# OLED_Board.net
KiCad netlist of a schematic drawn in EAGLE
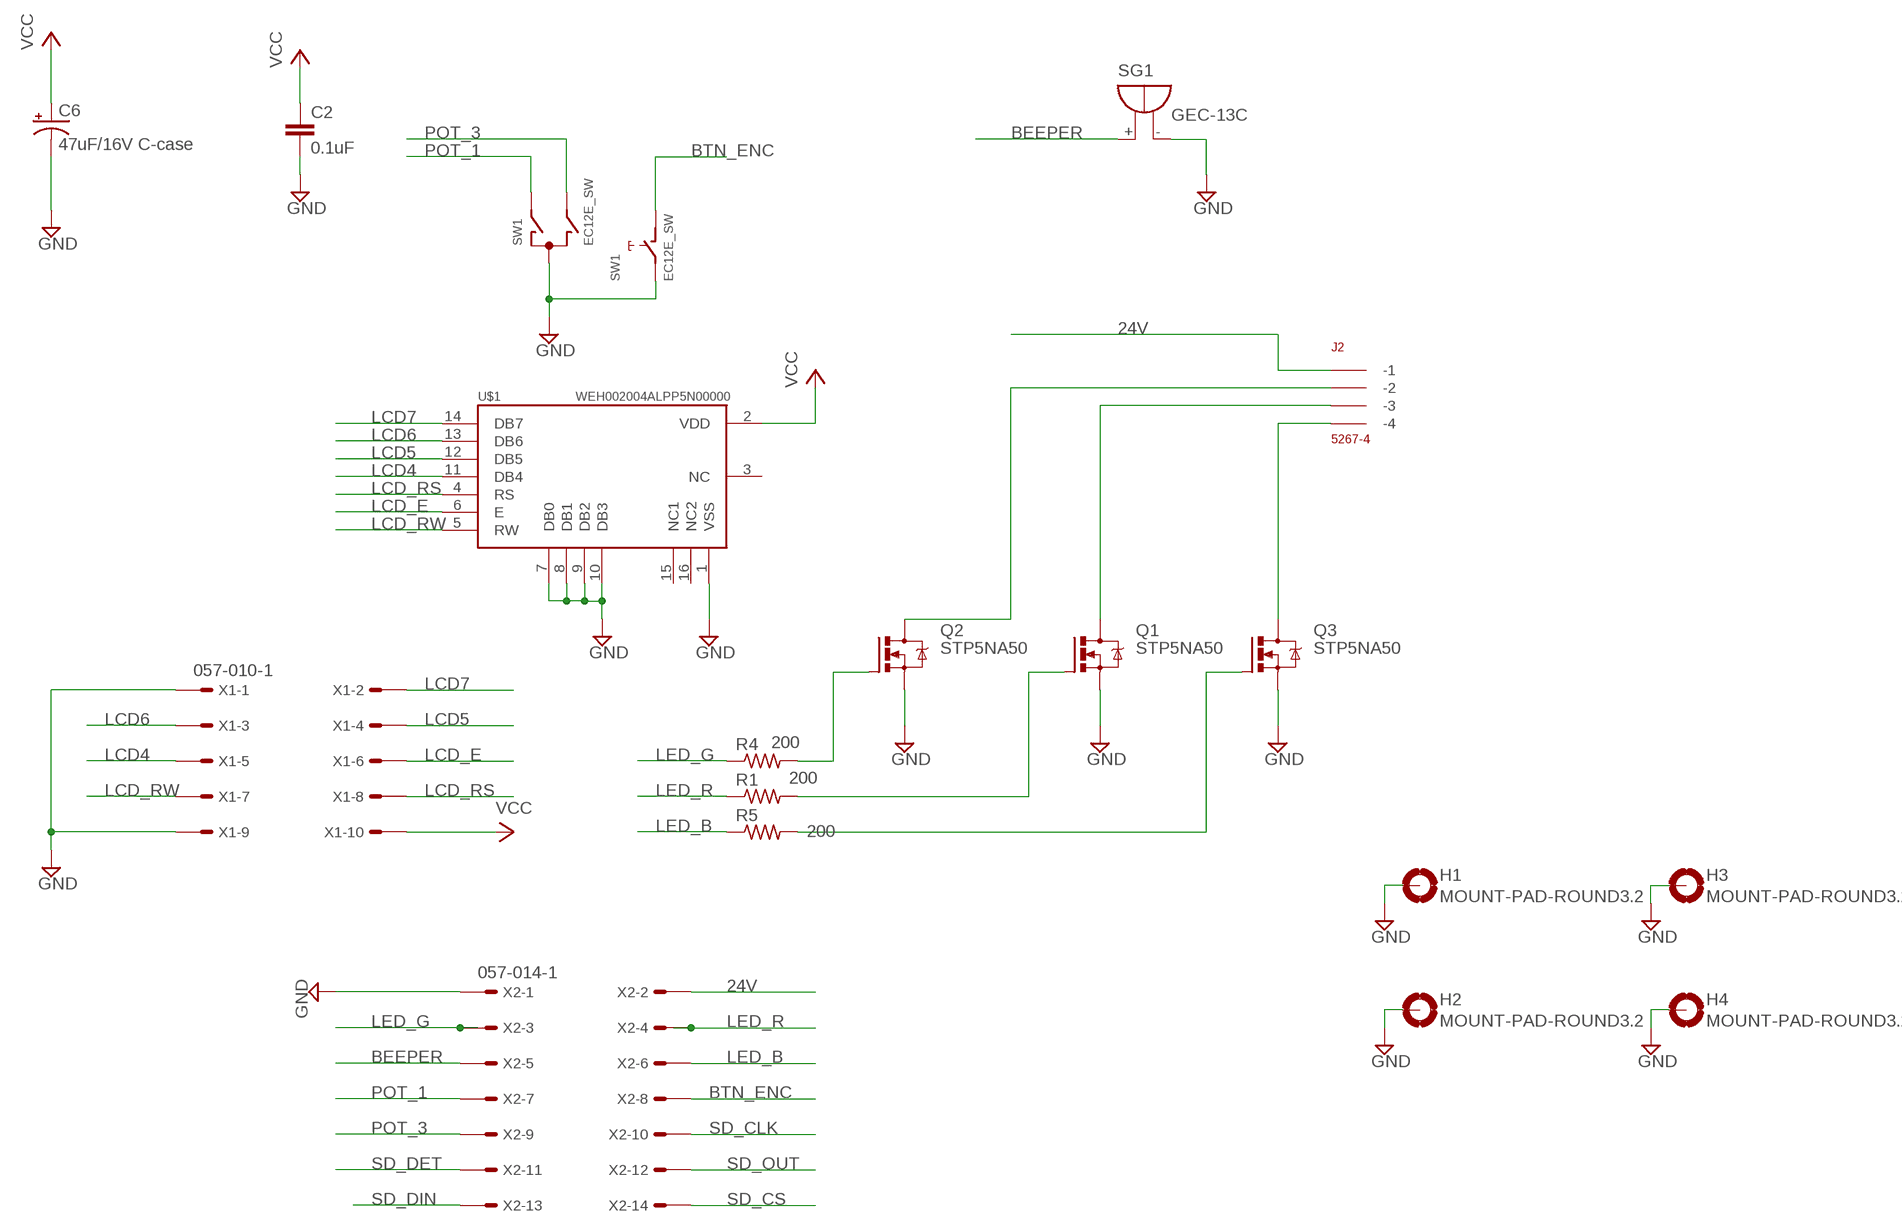
[diagram p0: schematic, sheet 1]
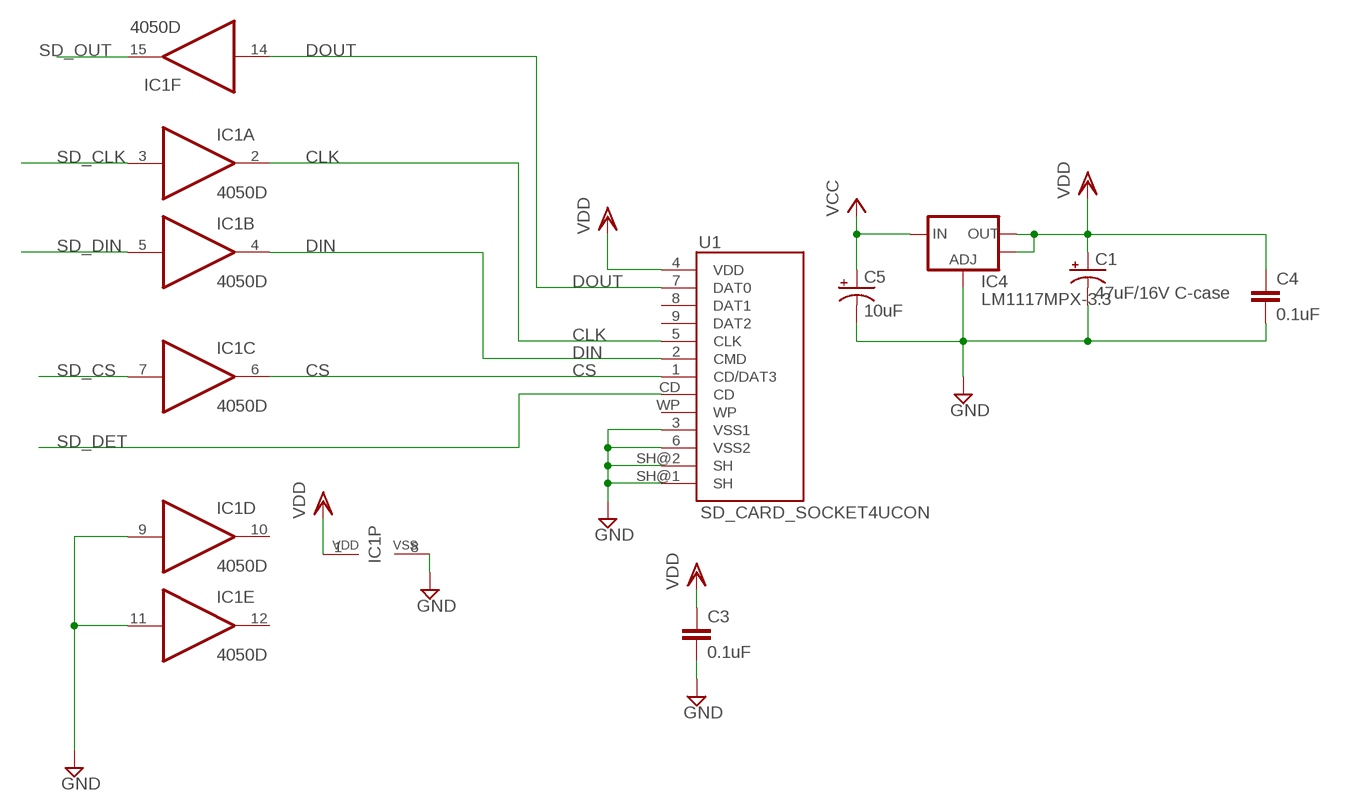
[diagram p1: schematic, sheet 2]

(export (version "E")
  (design (tool "Eeschema 10.0.6"))
  (components
    (comp (ref "C1")
      (value "47uF/16V C-case")
      (footprint "eagle-import:EIA6032")
      (libsource (lib "eagle-import") (part "CAP_POL6032"))
    )
    (comp (ref "C3")
      (value "0.1uF")
      (footprint "eagle-import:C0805")
      (libsource (lib "eagle-import") (part "resistor_C-EUC0805"))
    )
    (comp (ref "C4")
      (value "0.1uF")
      (footprint "eagle-import:C0805")
      (libsource (lib "eagle-import") (part "resistor_C-EUC0805"))
    )
    (comp (ref "C5")
      (value "10uF")
      (footprint "eagle-import:CT3216")
      (libsource (lib "eagle-import") (part "CPOL-USCT3216"))
    )
    (comp (ref "IC1")
      (value "4050D")
      (footprint "eagle-import:SO16")
      (libsource (lib "eagle-import") (part "4050D"))
    )
    (comp (ref "IC4")
      (value "LM1117MPX-3.3")
      (footprint "eagle-import:SOT223")
      (libsource (lib "eagle-import") (part "V_REG_LM1117SOT223"))
    )
    (comp (ref "U1")
      (value "SD_CARD_SOCKET4UCON")
      (footprint "eagle-import:SDCARD_4UCONN")
      (libsource (lib "eagle-import") (part "SD_CARD_SOCKET4UCON"))
    )
    (comp (ref "C2")
      (value "0.1uF")
      (footprint "eagle-import:C0805")
      (libsource (lib "eagle-import") (part "C-EUC0805"))
    )
    (comp (ref "C6")
      (value "47uF/16V C-case")
      (footprint "eagle-import:EIA6032")
      (libsource (lib "eagle-import") (part "CAP_POL6032"))
    )
    (comp (ref "H1")
      (value "MOUNT-PAD-ROUND3.2")
      (footprint "eagle-import:3,2-PAD")
      (libsource (lib "eagle-import") (part "MOUNT-PAD-ROUND3.2"))
    )
    (comp (ref "H2")
      (value "MOUNT-PAD-ROUND3.2")
      (footprint "eagle-import:3,2-PAD")
      (libsource (lib "eagle-import") (part "MOUNT-PAD-ROUND3.2"))
    )
    (comp (ref "H3")
      (value "MOUNT-PAD-ROUND3.2")
      (footprint "eagle-import:3,2-PAD")
      (libsource (lib "eagle-import") (part "MOUNT-PAD-ROUND3.2"))
    )
    (comp (ref "H4")
      (value "MOUNT-PAD-ROUND3.2")
      (footprint "eagle-import:3,2-PAD")
      (libsource (lib "eagle-import") (part "MOUNT-PAD-ROUND3.2"))
    )
    (comp (ref "J2")
      (value "5267-4")
      (footprint "eagle-import:5267-4")
      (libsource (lib "eagle-import") (part "5267-4"))
    )
    (comp (ref "Q1")
      (value "STP5NA50")
      (footprint "eagle-import:TO220BV")
      (libsource (lib "eagle-import") (part "STP5NA50"))
    )
    (comp (ref "Q2")
      (value "STP5NA50")
      (footprint "eagle-import:TO220BV")
      (libsource (lib "eagle-import") (part "STP5NA50"))
    )
    (comp (ref "Q3")
      (value "STP5NA50")
      (footprint "eagle-import:TO220BV")
      (libsource (lib "eagle-import") (part "STP5NA50"))
    )
    (comp (ref "R1")
      (value "200")
      (footprint "eagle-import:R2012")
      (libsource (lib "eagle-import") (part "R-US_R2012"))
    )
    (comp (ref "R4")
      (value "200")
      (footprint "eagle-import:R2012")
      (libsource (lib "eagle-import") (part "R-US_R2012"))
    )
    (comp (ref "R5")
      (value "200")
      (footprint "eagle-import:R2012")
      (libsource (lib "eagle-import") (part "R-US_R2012"))
    )
    (comp (ref "SG1")
      (value "GEC-13C")
      (footprint "eagle-import:F_TMB")
      (libsource (lib "eagle-import") (part "F/TMB"))
    )
    (comp (ref "SW1")
      (value "EC12E_SW")
      (footprint "eagle-import:ALPS_EC12E_SW")
      (fields (field (name "MPN") "EC12E2424407"))
      (libsource (lib "eagle-import") (part "EC12E_SW"))
    )
    (comp (ref "U$1")
      (value "OLED")
      (footprint "eagle-import:WEH002004ALPP5N00000")
      (libsource (lib "eagle-import") (part "OLED"))
    )
    (comp (ref "X1")
      (value "057-010-1")
      (footprint "eagle-import:057-010-1")
      (libsource (lib "eagle-import") (part "057-010-1"))
    )
    (comp (ref "X2")
      (value "057-014-1")
      (footprint "eagle-import:057-014-1")
      (libsource (lib "eagle-import") (part "057-014-1"))
    )
  )
  (nets
    (net (code "1") (name "24V") (class "Default")
      (node (ref "J2") (pin "P$1") (pinfunction "-1_P$1") (pintype "bidirectional"))
      (node (ref "X2") (pin "2") (pinfunction "S_2") (pintype "passive"))
    )
    (net (code "2") (name "BEEPER") (class "Default")
      (node (ref "SG1") (pin "+") (pinfunction "+_+") (pintype "passive"))
      (node (ref "X2") (pin "5") (pinfunction "S_5") (pintype "passive"))
    )
    (net (code "3") (name "BTN_ENC") (class "Default")
      (node (ref "SW1") (pin "D") (pinfunction "1_D") (pintype "passive"))
      (node (ref "X2") (pin "8") (pinfunction "S_8") (pintype "passive"))
    )
    (net (code "4") (name "CLK") (class "Default")
      (node (ref "IC1") (pin "2") (pinfunction "O_2") (pintype "output"))
      (node (ref "U1") (pin "5") (pinfunction "CLK_5") (pintype "bidirectional"))
    )
    (net (code "5") (name "CS") (class "Default")
      (node (ref "IC1") (pin "6") (pinfunction "O_6") (pintype "output"))
      (node (ref "U1") (pin "1") (pinfunction "CD/DAT3_1") (pintype "bidirectional"))
    )
    (net (code "6") (name "DIN") (class "Default")
      (node (ref "IC1") (pin "4") (pinfunction "O_4") (pintype "output"))
      (node (ref "U1") (pin "2") (pinfunction "CMD_2") (pintype "bidirectional"))
    )
    (net (code "7") (name "DOUT") (class "Default")
      (node (ref "IC1") (pin "14") (pinfunction "I_14") (pintype "input"))
      (node (ref "U1") (pin "7") (pinfunction "DAT0_7") (pintype "bidirectional"))
    )
    (net (code "8") (name "GND") (class "Default")
      (node (ref "C1") (pin "P$2") (pinfunction "-_P$2") (pintype "passive"))
      (node (ref "C2") (pin "2") (pinfunction "2_2") (pintype "passive"))
      (node (ref "C3") (pin "2") (pinfunction "2_2") (pintype "passive"))
      (node (ref "C4") (pin "2") (pinfunction "2_2") (pintype "passive"))
      (node (ref "C5") (pin "-") (pinfunction "-_-") (pintype "passive"))
      (node (ref "C6") (pin "P$2") (pinfunction "-_P$2") (pintype "passive"))
      (node (ref "H1") (pin "B3,2") (pinfunction "MOUNT_B3,2") (pintype "passive"))
      (node (ref "H2") (pin "B3,2") (pinfunction "MOUNT_B3,2") (pintype "passive"))
      (node (ref "H3") (pin "B3,2") (pinfunction "MOUNT_B3,2") (pintype "passive"))
      (node (ref "H4") (pin "B3,2") (pinfunction "MOUNT_B3,2") (pintype "passive"))
      (node (ref "IC1") (pin "11") (pinfunction "I_11") (pintype "input"))
      (node (ref "IC1") (pin "8") (pinfunction "VSS_8") (pintype "power_in"))
      (node (ref "IC1") (pin "9") (pinfunction "I_9") (pintype "input"))
      (node (ref "IC4") (pin "1") (pinfunction "ADJ_1") (pintype "input"))
      (node (ref "Q1") (pin "S") (pinfunction "S_S") (pintype "passive"))
      (node (ref "Q2") (pin "S") (pinfunction "S_S") (pintype "passive"))
      (node (ref "Q3") (pin "S") (pinfunction "S_S") (pintype "passive"))
      (node (ref "SG1") (pin "-") (pinfunction "-_-") (pintype "passive"))
      (node (ref "SW1") (pin "C") (pinfunction "C_C") (pintype "passive"))
      (node (ref "SW1") (pin "E") (pinfunction "2_E") (pintype "passive"))
      (node (ref "U$1") (pin "1") (pinfunction "VSS_1") (pintype "bidirectional"))
      (node (ref "U$1") (pin "10") (pinfunction "DB3_10") (pintype "bidirectional"))
      (node (ref "U$1") (pin "7") (pinfunction "DB0_7") (pintype "bidirectional"))
      (node (ref "U$1") (pin "8") (pinfunction "DB1_8") (pintype "bidirectional"))
      (node (ref "U$1") (pin "9") (pinfunction "DB2_9") (pintype "bidirectional"))
      (node (ref "U1") (pin "3") (pinfunction "VSS1_3") (pintype "power_in"))
      (node (ref "U1") (pin "6") (pinfunction "VSS2_6") (pintype "power_in"))
      (node (ref "U1") (pin "SH@1") (pinfunction "SH_SH@1") (pintype "bidirectional"))
      (node (ref "U1") (pin "SH@2") (pinfunction "SH_SH@2") (pintype "bidirectional"))
      (node (ref "X1") (pin "1") (pinfunction "S_1") (pintype "passive"))
      (node (ref "X1") (pin "9") (pinfunction "S_9") (pintype "passive"))
      (node (ref "X2") (pin "1") (pinfunction "S_1") (pintype "passive"))
    )
    (net (code "9") (name "LCD4") (class "Default")
      (node (ref "U$1") (pin "11") (pinfunction "DB4_11") (pintype "bidirectional"))
      (node (ref "X1") (pin "5") (pinfunction "S_5") (pintype "passive"))
    )
    (net (code "10") (name "LCD5") (class "Default")
      (node (ref "U$1") (pin "12") (pinfunction "DB5_12") (pintype "bidirectional"))
      (node (ref "X1") (pin "4") (pinfunction "S_4") (pintype "passive"))
    )
    (net (code "11") (name "LCD6") (class "Default")
      (node (ref "U$1") (pin "13") (pinfunction "DB6_13") (pintype "bidirectional"))
      (node (ref "X1") (pin "3") (pinfunction "S_3") (pintype "passive"))
    )
    (net (code "12") (name "LCD7") (class "Default")
      (node (ref "U$1") (pin "14") (pinfunction "DB7_14") (pintype "bidirectional"))
      (node (ref "X1") (pin "2") (pinfunction "S_2") (pintype "passive"))
    )
    (net (code "13") (name "LCD_E") (class "Default")
      (node (ref "U$1") (pin "6") (pinfunction "E_6") (pintype "bidirectional"))
      (node (ref "X1") (pin "6") (pinfunction "S_6") (pintype "passive"))
    )
    (net (code "14") (name "LCD_RS") (class "Default")
      (node (ref "U$1") (pin "4") (pinfunction "RS_4") (pintype "bidirectional"))
      (node (ref "X1") (pin "8") (pinfunction "S_8") (pintype "passive"))
    )
    (net (code "15") (name "LCD_RW") (class "Default")
      (node (ref "U$1") (pin "5") (pinfunction "RW_5") (pintype "bidirectional"))
      (node (ref "X1") (pin "7") (pinfunction "S_7") (pintype "passive"))
    )
    (net (code "16") (name "LED_B") (class "Default")
      (node (ref "R5") (pin "1") (pinfunction "1_1") (pintype "passive"))
      (node (ref "X2") (pin "6") (pinfunction "S_6") (pintype "passive"))
    )
    (net (code "17") (name "LED_G") (class "Default")
      (node (ref "R4") (pin "1") (pinfunction "1_1") (pintype "passive"))
      (node (ref "X2") (pin "3") (pinfunction "S_3") (pintype "passive"))
    )
    (net (code "18") (name "LED_R") (class "Default")
      (node (ref "R1") (pin "1") (pinfunction "1_1") (pintype "passive"))
      (node (ref "X2") (pin "4") (pinfunction "S_4") (pintype "passive"))
    )
    (net (code "19") (name "Net-(J2--2)") (class "Default")
      (node (ref "J2") (pin "P$2") (pinfunction "-2_P$2") (pintype "bidirectional"))
      (node (ref "Q2") (pin "D") (pinfunction "D_D") (pintype "passive"))
    )
    (net (code "20") (name "Net-(J2--3)") (class "Default")
      (node (ref "J2") (pin "P$3") (pinfunction "-3_P$3") (pintype "bidirectional"))
      (node (ref "Q1") (pin "D") (pinfunction "D_D") (pintype "passive"))
    )
    (net (code "21") (name "Net-(J2--4)") (class "Default")
      (node (ref "J2") (pin "P$4") (pinfunction "-4_P$4") (pintype "bidirectional"))
      (node (ref "Q3") (pin "D") (pinfunction "D_D") (pintype "passive"))
    )
    (net (code "22") (name "Net-(Q1-PadG)") (class "Default")
      (node (ref "Q1") (pin "G") (pinfunction "G_G") (pintype "passive"))
      (node (ref "R1") (pin "2") (pinfunction "2_2") (pintype "passive"))
    )
    (net (code "23") (name "Net-(Q2-PadG)") (class "Default")
      (node (ref "Q2") (pin "G") (pinfunction "G_G") (pintype "passive"))
      (node (ref "R4") (pin "2") (pinfunction "2_2") (pintype "passive"))
    )
    (net (code "24") (name "Net-(Q3-PadG)") (class "Default")
      (node (ref "Q3") (pin "G") (pinfunction "G_G") (pintype "passive"))
      (node (ref "R5") (pin "2") (pinfunction "2_2") (pintype "passive"))
    )
    (net (code "25") (name "POT_1") (class "Default")
      (node (ref "SW1") (pin "A") (pinfunction "A_A") (pintype "passive"))
      (node (ref "X2") (pin "7") (pinfunction "S_7") (pintype "passive"))
    )
    (net (code "26") (name "POT_3") (class "Default")
      (node (ref "SW1") (pin "B") (pinfunction "B_B") (pintype "passive"))
      (node (ref "X2") (pin "9") (pinfunction "S_9") (pintype "passive"))
    )
    (net (code "27") (name "SD_CLK") (class "Default")
      (node (ref "IC1") (pin "3") (pinfunction "I_3") (pintype "input"))
      (node (ref "X2") (pin "10") (pinfunction "S_10") (pintype "passive"))
    )
    (net (code "28") (name "SD_CS") (class "Default")
      (node (ref "IC1") (pin "7") (pinfunction "I_7") (pintype "input"))
      (node (ref "X2") (pin "14") (pinfunction "S_14") (pintype "passive"))
    )
    (net (code "29") (name "SD_DET") (class "Default")
      (node (ref "U1") (pin "CD") (pinfunction "CD_CD") (pintype "bidirectional"))
      (node (ref "X2") (pin "11") (pinfunction "S_11") (pintype "passive"))
    )
    (net (code "30") (name "SD_DIN") (class "Default")
      (node (ref "IC1") (pin "5") (pinfunction "I_5") (pintype "input"))
      (node (ref "X2") (pin "13") (pinfunction "S_13") (pintype "passive"))
    )
    (net (code "31") (name "SD_OUT") (class "Default")
      (node (ref "IC1") (pin "15") (pinfunction "O_15") (pintype "output"))
      (node (ref "X2") (pin "12") (pinfunction "S_12") (pintype "passive"))
    )
    (net (code "32") (name "VCC") (class "Default")
      (node (ref "C2") (pin "1") (pinfunction "1_1") (pintype "passive"))
      (node (ref "C5") (pin "+") (pinfunction "+_+") (pintype "passive"))
      (node (ref "C6") (pin "P$1") (pinfunction "+_P$1") (pintype "passive"))
      (node (ref "IC4") (pin "3") (pinfunction "IN_3") (pintype "input"))
      (node (ref "U$1") (pin "2") (pinfunction "VDD_2") (pintype "bidirectional"))
      (node (ref "X1") (pin "10") (pinfunction "S_10") (pintype "passive"))
    )
    (net (code "33") (name "VDD") (class "Default")
      (node (ref "C1") (pin "P$1") (pinfunction "+_P$1") (pintype "passive"))
      (node (ref "C3") (pin "1") (pinfunction "1_1") (pintype "passive"))
      (node (ref "C4") (pin "1") (pinfunction "1_1") (pintype "passive"))
      (node (ref "IC1") (pin "1") (pinfunction "VDD_1") (pintype "power_in"))
      (node (ref "IC4") (pin "2") (pinfunction "OUT_2") (pintype "output"))
      (node (ref "IC4") (pin "4") (pinfunction "OUT_4") (pintype "output"))
      (node (ref "U1") (pin "4") (pinfunction "VDD_4") (pintype "power_in"))
    )
    (net (code "34") (name "unconnected-(IC1D-O-Pad10)") (class "Default")
      (node (ref "IC1") (pin "10") (pinfunction "O_10") (pintype "output"))
    )
    (net (code "35") (name "unconnected-(IC1E-O-Pad12)") (class "Default")
      (node (ref "IC1") (pin "12") (pinfunction "O_12") (pintype "output"))
    )
    (net (code "36") (name "unconnected-(U$1-NC-Pad3)") (class "Default")
      (node (ref "U$1") (pin "3") (pinfunction "NC_3") (pintype "bidirectional"))
    )
    (net (code "37") (name "unconnected-(U$1-NC1-Pad15)") (class "Default")
      (node (ref "U$1") (pin "15") (pinfunction "NC1_15") (pintype "bidirectional"))
    )
    (net (code "38") (name "unconnected-(U$1-NC2-Pad16)") (class "Default")
      (node (ref "U$1") (pin "16") (pinfunction "NC2_16") (pintype "bidirectional"))
    )
    (net (code "39") (name "unconnected-(U1-DAT1-Pad8)") (class "Default")
      (node (ref "U1") (pin "8") (pinfunction "DAT1_8") (pintype "bidirectional"))
    )
    (net (code "40") (name "unconnected-(U1-DAT2-Pad9)") (class "Default")
      (node (ref "U1") (pin "9") (pinfunction "DAT2_9") (pintype "bidirectional"))
    )
    (net (code "41") (name "unconnected-(U1-PadWP)") (class "Default")
      (node (ref "U1") (pin "WP") (pinfunction "WP_WP") (pintype "bidirectional"))
    )
  )
)
